# MainBoard.net
KiCad netlist of a schematic drawn in Altium Designer
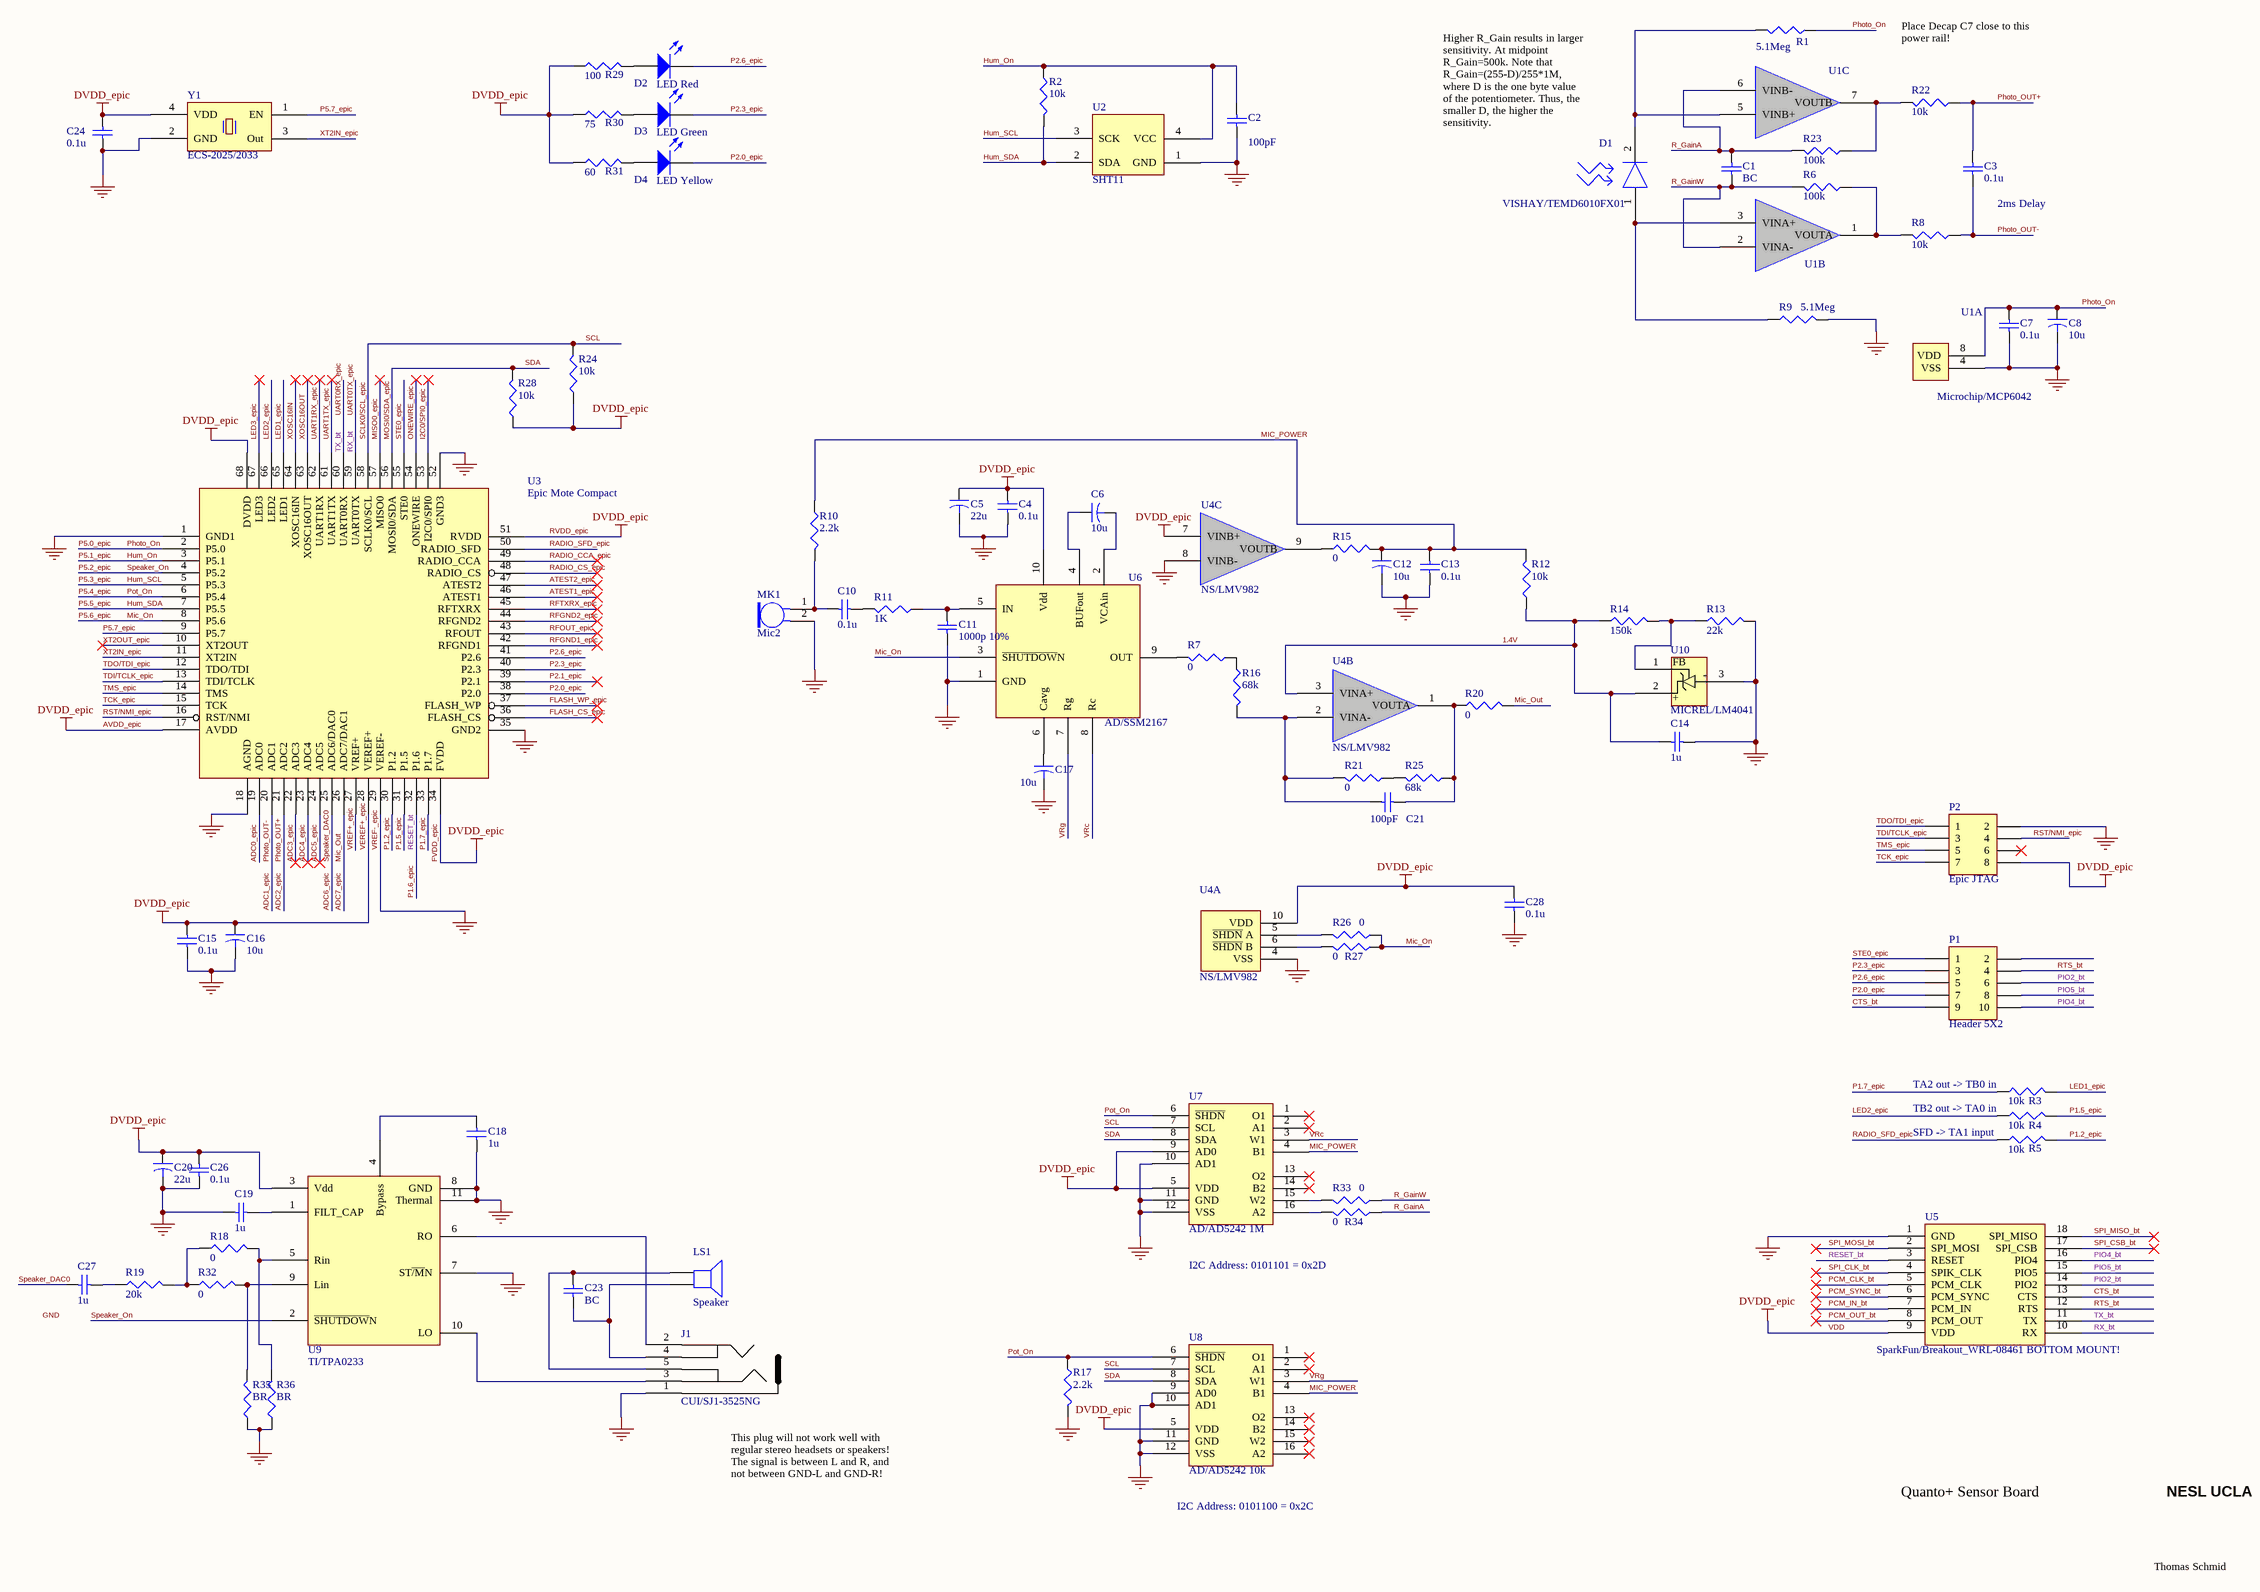
[diagram p0: MainBoard.SchDoc]

(export (version "E")
  (design (tool "Eeschema 10.0.6"))
  (components
    (comp (ref "C1")
      (value "BC")
      (footprint "CC1608-0603")
      (description "Capacitor")
      (fields (field (name "Comment") "Cap") (field (name "PUBLISHER") "Altium Limited"))
      (libsource (lib "Miscellaneous Devices") (part "Cap"))
    )
    (comp (ref "C2")
      (value "100pF")
      (footprint "CC1608-0603")
      (description "Capacitor")
      (fields (field (name "Comment") "Cap") (field (name "PUBLISHER") "Altium Limited"))
      (libsource (lib "Miscellaneous Devices") (part "Cap"))
    )
    (comp (ref "C3")
      (value "0.1u")
      (footprint "CC1608-0603")
      (description "Capacitor")
      (fields (field (name "Comment") "Cap") (field (name "PUBLISHER") "Altium Limited"))
      (libsource (lib "Miscellaneous Devices") (part "Cap"))
    )
    (comp (ref "C4")
      (value "0.1u")
      (footprint "CC1608-0603")
      (description "Capacitor")
      (fields (field (name "Comment") "Cap") (field (name "PUBLISHER") "Altium Limited"))
      (libsource (lib "Miscellaneous Devices") (part "Cap"))
    )
    (comp (ref "C5")
      (value "22u")
      (footprint "CC3216-1206")
      (description "Capacitor")
      (fields (field (name "Comment") "Cap2") (field (name "PUBLISHER") "Altium Limited"))
      (libsource (lib "Miscellaneous Devices") (part "Cap2"))
    )
    (comp (ref "C6")
      (value "10u")
      (footprint "CC1608-0603")
      (description "Capacitor")
      (fields (field (name "Comment") "Cap2") (field (name "PUBLISHER") "Altium Limited"))
      (libsource (lib "") (part "Cap2_1"))
    )
    (comp (ref "C7")
      (value "0.1u")
      (footprint "CC1608-0603")
      (description "Capacitor")
      (fields (field (name "Comment") "Cap") (field (name "PUBLISHER") "Altium Limited"))
      (libsource (lib "Miscellaneous Devices") (part "Cap"))
    )
    (comp (ref "C8")
      (value "10u")
      (footprint "CC1608-0603")
      (description "Capacitor")
      (fields (field (name "Comment") "Cap2") (field (name "PUBLISHER") "Altium Limited"))
      (libsource (lib "Miscellaneous Devices") (part "Cap2"))
    )
    (comp (ref "C10")
      (value "0.1u")
      (footprint "CC1608-0603")
      (description "Capacitor")
      (fields (field (name "Comment") "Cap") (field (name "PUBLISHER") "Altium Limited"))
      (libsource (lib "Miscellaneous Devices") (part "Cap"))
    )
    (comp (ref "C11")
      (value "1000p 10%")
      (footprint "CC1608-0603")
      (description "Capacitor")
      (fields (field (name "Comment") "Cap") (field (name "PUBLISHER") "Altium Limited"))
      (libsource (lib "Miscellaneous Devices") (part "Cap"))
    )
    (comp (ref "C12")
      (value "10u")
      (footprint "CC1608-0603")
      (description "Capacitor")
      (fields (field (name "Comment") "Cap2") (field (name "PUBLISHER") "Altium Limited"))
      (libsource (lib "Miscellaneous Devices") (part "Cap2"))
    )
    (comp (ref "C13")
      (value "0.1u")
      (footprint "CC1608-0603")
      (description "Capacitor")
      (fields (field (name "Comment") "Cap") (field (name "PUBLISHER") "Altium Limited"))
      (libsource (lib "Miscellaneous Devices") (part "Cap"))
    )
    (comp (ref "C14")
      (value "1u")
      (footprint "CC1608-0603")
      (description "Capacitor")
      (fields (field (name "Comment") "Cap") (field (name "PUBLISHER") "Altium Limited"))
      (libsource (lib "") (part "Cap_1"))
    )
    (comp (ref "C15")
      (value "0.1u")
      (footprint "CC1608-0603")
      (description "Capacitor")
      (fields (field (name "Comment") "Cap") (field (name "PUBLISHER") "Altium Limited"))
      (libsource (lib "Miscellaneous Devices") (part "Cap"))
    )
    (comp (ref "C16")
      (value "10u")
      (footprint "CC1608-0603")
      (description "Capacitor")
      (fields (field (name "Comment") "Cap2") (field (name "PUBLISHER") "Altium Limited"))
      (libsource (lib "Miscellaneous Devices") (part "Cap2"))
    )
    (comp (ref "C17")
      (value "10u")
      (footprint "CC1608-0603")
      (description "Capacitor")
      (fields (field (name "Comment") "Cap2") (field (name "PUBLISHER") "Altium Limited"))
      (libsource (lib "") (part "Cap2_1"))
    )
    (comp (ref "C18")
      (value "1u")
      (footprint "CC1608-0603")
      (description "Capacitor")
      (fields (field (name "Comment") "Cap") (field (name "PUBLISHER") "Altium Limited"))
      (libsource (lib "Miscellaneous Devices") (part "Cap"))
    )
    (comp (ref "C19")
      (value "1u")
      (footprint "CC1608-0603")
      (description "Capacitor")
      (fields (field (name "Comment") "Cap") (field (name "PUBLISHER") "Altium Limited"))
      (libsource (lib "") (part "Cap_1"))
    )
    (comp (ref "C20")
      (value "22u")
      (footprint "CC3216-1206")
      (description "Capacitor")
      (fields (field (name "Comment") "Cap2") (field (name "PUBLISHER") "Altium Limited"))
      (libsource (lib "Miscellaneous Devices") (part "Cap2"))
    )
    (comp (ref "C21")
      (value "100pF")
      (footprint "CC1608-0603")
      (description "Capacitor")
      (fields (field (name "Comment") "Cap") (field (name "PUBLISHER") "Altium Limited"))
      (libsource (lib "Miscellaneous Devices") (part "Cap"))
    )
    (comp (ref "C23")
      (value "BC")
      (footprint "CC1608-0603")
      (description "Capacitor")
      (fields (field (name "Comment") "Cap") (field (name "PUBLISHER") "Altium Limited"))
      (libsource (lib "Miscellaneous Devices") (part "Cap"))
    )
    (comp (ref "C24")
      (value "0.1u")
      (footprint "CC1608-0603")
      (description "Capacitor")
      (fields (field (name "Comment") "Cap") (field (name "PUBLISHER") "Altium Limited"))
      (libsource (lib "Miscellaneous Devices") (part "Cap"))
    )
    (comp (ref "C26")
      (value "0.1u")
      (footprint "CC1608-0603")
      (description "Capacitor")
      (fields (field (name "Comment") "Cap") (field (name "PUBLISHER") "Altium Limited"))
      (libsource (lib "Miscellaneous Devices") (part "Cap"))
    )
    (comp (ref "C27")
      (value "1u")
      (footprint "CC1608-0603")
      (description "Capacitor")
      (fields (field (name "Comment") "Cap") (field (name "PUBLISHER") "Altium Limited"))
      (libsource (lib "Miscellaneous Devices") (part "Cap"))
    )
    (comp (ref "C28")
      (value "0.1u")
      (footprint "CC1608-0603")
      (description "Capacitor")
      (fields (field (name "Comment") "Cap") (field (name "PUBLISHER") "Altium Limited"))
      (libsource (lib "Miscellaneous Devices") (part "Cap"))
    )
    (comp (ref "D1")
      (value "VISHAY/TEMD6010FX01")
      (footprint "VISHAY/TEMD6010FX01")
      (libsource (lib "Schematics") (part "VISHAY/TEMD6010FX01"))
    )
    (comp (ref "D2")
      (value "LED Red")
      (footprint "LiteOn/LTST-C150")
      (description "Typical RED, GREEN, YELLOW, AMBER GaAs LED")
      (fields (field (name "PUBLISHER") "Altium Limited"))
      (libsource (lib "Miscellaneous Devices") (part "LED2"))
    )
    (comp (ref "D3")
      (value "LED Green")
      (footprint "LiteOn/LTST-C150")
      (description "Typical RED, GREEN, YELLOW, AMBER GaAs LED")
      (fields (field (name "PUBLISHER") "Altium Limited"))
      (libsource (lib "Miscellaneous Devices") (part "LED2"))
    )
    (comp (ref "D4")
      (value "LED Yellow")
      (footprint "LiteOn/LTST-C150")
      (description "Typical RED, GREEN, YELLOW, AMBER GaAs LED")
      (fields (field (name "PUBLISHER") "Altium Limited"))
      (libsource (lib "Miscellaneous Devices") (part "LED2"))
    )
    (comp (ref "J1")
      (value "CUI/SJ1-3525NG")
      (footprint "CUI/PHONE_JACK_3.5mm")
      (libsource (lib "Schematics") (part "CUI/SJ1-3525NG"))
    )
    (comp (ref "LS1")
      (value "Speaker")
      (footprint "PIN2")
      (description "Loudspeaker")
      (fields (field (name "PUBLISHER") "Altium Limited"))
      (libsource (lib "Miscellaneous Devices") (part "Speaker"))
    )
    (comp (ref "MK1")
      (value "Mic2")
      (footprint "CUIINC/CMA-4544PF-W")
      (description "Microphone")
      (fields (field (name "PUBLISHER") "Altium Limited"))
      (libsource (lib "Miscellaneous Devices") (part "Mic2"))
    )
    (comp (ref "P1")
      (value "Header 5X2")
      (footprint "HDR2X5")
      (description "Header, 5-Pin, Dual row")
      (fields (field (name "PUBLISHER") "Altium Limited"))
      (libsource (lib "Miscellaneous Connectors") (part "Header 5X2"))
    )
    (comp (ref "P2")
      (value "Epic JTAG")
      (footprint "Thomas/Header 2x4 2mm")
      (description "Header, 4-Pin, Dual row")
      (fields (field (name "PUBLISHER") "Altium Limited"))
      (libsource (lib "Miscellaneous Connectors") (part "Header 4X2"))
    )
    (comp (ref "R1")
      (value "5.1Meg")
      (footprint "CR1608-0603")
      (description "Resistor")
      (fields (field (name "Comment") "Res3") (field (name "PUBLISHER") "Altium Limited"))
      (libsource (lib "Miscellaneous Devices") (part "Res3"))
    )
    (comp (ref "R2")
      (value "10k")
      (footprint "CR1608-0603")
      (description "Resistor")
      (fields (field (name "Comment") "Res3") (field (name "PUBLISHER") "Altium Limited"))
      (libsource (lib "Miscellaneous Devices") (part "Res3"))
    )
    (comp (ref "R3")
      (value "10k")
      (footprint "CR1608-0603")
      (description "Resistor")
      (fields (field (name "Comment") "Res3") (field (name "PUBLISHER") "Altium Limited"))
      (libsource (lib "Miscellaneous Devices") (part "Res3"))
    )
    (comp (ref "R4")
      (value "10k")
      (footprint "CR1608-0603")
      (description "Resistor")
      (fields (field (name "Comment") "Res3") (field (name "PUBLISHER") "Altium Limited"))
      (libsource (lib "Miscellaneous Devices") (part "Res3"))
    )
    (comp (ref "R5")
      (value "10k")
      (footprint "CR1608-0603")
      (description "Resistor")
      (fields (field (name "Comment") "Res3") (field (name "PUBLISHER") "Altium Limited"))
      (libsource (lib "Miscellaneous Devices") (part "Res3"))
    )
    (comp (ref "R6")
      (value "100k")
      (footprint "CR1608-0603")
      (description "Resistor")
      (fields (field (name "Comment") "Res3") (field (name "PUBLISHER") "Altium Limited"))
      (libsource (lib "Miscellaneous Devices") (part "Res3"))
    )
    (comp (ref "R7")
      (value "0")
      (footprint "CR1608-0603")
      (description "Resistor")
      (fields (field (name "Comment") "Res3") (field (name "PUBLISHER") "Altium Limited"))
      (libsource (lib "Miscellaneous Devices") (part "Res3"))
    )
    (comp (ref "R8")
      (value "10k")
      (footprint "CR1608-0603")
      (description "Resistor")
      (fields (field (name "Comment") "Res3") (field (name "PUBLISHER") "Altium Limited"))
      (libsource (lib "Miscellaneous Devices") (part "Res3"))
    )
    (comp (ref "R9")
      (value "5.1Meg")
      (footprint "CR1608-0603")
      (description "Resistor")
      (fields (field (name "Comment") "Res3") (field (name "PUBLISHER") "Altium Limited"))
      (libsource (lib "Miscellaneous Devices") (part "Res3"))
    )
    (comp (ref "R10")
      (value "2.2k")
      (footprint "CR1608-0603")
      (description "Resistor")
      (fields (field (name "Comment") "Res3") (field (name "PUBLISHER") "Altium Limited"))
      (libsource (lib "Miscellaneous Devices") (part "Res3"))
    )
    (comp (ref "R11")
      (value "1K")
      (footprint "CR1608-0603")
      (description "Resistor")
      (fields (field (name "Comment") "Res3") (field (name "PUBLISHER") "Altium Limited"))
      (libsource (lib "Miscellaneous Devices") (part "Res3"))
    )
    (comp (ref "R12")
      (value "10k")
      (footprint "CR1608-0603")
      (description "Resistor")
      (fields (field (name "Comment") "Res3") (field (name "PUBLISHER") "Altium Limited"))
      (libsource (lib "Miscellaneous Devices") (part "Res3"))
    )
    (comp (ref "R13")
      (value "22k")
      (footprint "CR1608-0603")
      (description "Resistor")
      (fields (field (name "Comment") "Res3") (field (name "PUBLISHER") "Altium Limited"))
      (libsource (lib "Miscellaneous Devices") (part "Res3"))
    )
    (comp (ref "R14")
      (value "150k")
      (footprint "CR1608-0603")
      (description "Resistor")
      (fields (field (name "Comment") "Res3") (field (name "PUBLISHER") "Altium Limited"))
      (libsource (lib "Miscellaneous Devices") (part "Res3"))
    )
    (comp (ref "R15")
      (value "0")
      (footprint "CR1608-0603")
      (description "Resistor")
      (fields (field (name "Comment") "Res3") (field (name "PUBLISHER") "Altium Limited"))
      (libsource (lib "Miscellaneous Devices") (part "Res3"))
    )
    (comp (ref "R16")
      (value "68k")
      (footprint "CR1608-0603")
      (description "Resistor")
      (fields (field (name "Comment") "Res3") (field (name "PUBLISHER") "Altium Limited"))
      (libsource (lib "") (part "Res3_1"))
    )
    (comp (ref "R17")
      (value "2.2k")
      (footprint "CR1608-0603")
      (description "Resistor")
      (fields (field (name "Comment") "Res3") (field (name "PUBLISHER") "Altium Limited"))
      (libsource (lib "Miscellaneous Devices") (part "Res3"))
    )
    (comp (ref "R18")
      (value "0")
      (footprint "CR1608-0603")
      (description "Resistor")
      (fields (field (name "Comment") "Res3") (field (name "PUBLISHER") "Altium Limited"))
      (libsource (lib "Miscellaneous Devices") (part "Res3"))
    )
    (comp (ref "R19")
      (value "20k")
      (footprint "CR1608-0603")
      (description "Resistor")
      (fields (field (name "Comment") "Res3") (field (name "PUBLISHER") "Altium Limited"))
      (libsource (lib "Miscellaneous Devices") (part "Res3"))
    )
    (comp (ref "R20")
      (value "0")
      (footprint "CR1608-0603")
      (description "Resistor")
      (fields (field (name "Comment") "Res3") (field (name "PUBLISHER") "Altium Limited"))
      (libsource (lib "Miscellaneous Devices") (part "Res3"))
    )
    (comp (ref "R21")
      (value "0")
      (footprint "CR1608-0603")
      (description "Resistor")
      (fields (field (name "Comment") "Res3") (field (name "PUBLISHER") "Altium Limited"))
      (libsource (lib "Miscellaneous Devices") (part "Res3"))
    )
    (comp (ref "R22")
      (value "10k")
      (footprint "CR1608-0603")
      (description "Resistor")
      (fields (field (name "Comment") "Res3") (field (name "PUBLISHER") "Altium Limited"))
      (libsource (lib "Miscellaneous Devices") (part "Res3"))
    )
    (comp (ref "R23")
      (value "100k")
      (footprint "CR1608-0603")
      (description "Resistor")
      (fields (field (name "Comment") "Res3") (field (name "PUBLISHER") "Altium Limited"))
      (libsource (lib "Miscellaneous Devices") (part "Res3"))
    )
    (comp (ref "R24")
      (value "10k")
      (footprint "CR1608-0603")
      (description "Resistor")
      (fields (field (name "Comment") "Res3") (field (name "PUBLISHER") "Altium Limited"))
      (libsource (lib "Miscellaneous Devices") (part "Res3"))
    )
    (comp (ref "R25")
      (value "68k")
      (footprint "CR1608-0603")
      (description "Resistor")
      (fields (field (name "Comment") "Res3") (field (name "PUBLISHER") "Altium Limited"))
      (libsource (lib "Miscellaneous Devices") (part "Res3"))
    )
    (comp (ref "R26")
      (value "0")
      (footprint "CR1608-0603")
      (description "Resistor")
      (fields (field (name "Comment") "Res3") (field (name "PUBLISHER") "Altium Limited"))
      (libsource (lib "Miscellaneous Devices") (part "Res3"))
    )
    (comp (ref "R27")
      (value "0")
      (footprint "CR1608-0603")
      (description "Resistor")
      (fields (field (name "Comment") "Res3") (field (name "PUBLISHER") "Altium Limited"))
      (libsource (lib "Miscellaneous Devices") (part "Res3"))
    )
    (comp (ref "R28")
      (value "10k")
      (footprint "CR1608-0603")
      (description "Resistor")
      (fields (field (name "Comment") "Res3") (field (name "PUBLISHER") "Altium Limited"))
      (libsource (lib "Miscellaneous Devices") (part "Res3"))
    )
    (comp (ref "R29")
      (value "100")
      (footprint "CR1608-0603")
      (description "Resistor")
      (fields (field (name "Comment") "Res3") (field (name "PUBLISHER") "Altium Limited"))
      (libsource (lib "Miscellaneous Devices") (part "Res3"))
    )
    (comp (ref "R30")
      (value "75")
      (footprint "CR1608-0603")
      (description "Resistor")
      (fields (field (name "Comment") "Res3") (field (name "PUBLISHER") "Altium Limited"))
      (libsource (lib "Miscellaneous Devices") (part "Res3"))
    )
    (comp (ref "R31")
      (value "60")
      (footprint "CR1608-0603")
      (description "Resistor")
      (fields (field (name "Comment") "Res3") (field (name "PUBLISHER") "Altium Limited"))
      (libsource (lib "Miscellaneous Devices") (part "Res3"))
    )
    (comp (ref "R32")
      (value "0")
      (footprint "CR1608-0603")
      (description "Resistor")
      (fields (field (name "Comment") "Res3") (field (name "PUBLISHER") "Altium Limited"))
      (libsource (lib "Miscellaneous Devices") (part "Res3"))
    )
    (comp (ref "R33")
      (value "0")
      (footprint "CR1608-0603")
      (description "Resistor")
      (fields (field (name "Comment") "Res3") (field (name "PUBLISHER") "Altium Limited"))
      (libsource (lib "Miscellaneous Devices") (part "Res3"))
    )
    (comp (ref "R34")
      (value "0")
      (footprint "CR1608-0603")
      (description "Resistor")
      (fields (field (name "Comment") "Res3") (field (name "PUBLISHER") "Altium Limited"))
      (libsource (lib "Miscellaneous Devices") (part "Res3"))
    )
    (comp (ref "R35")
      (value "BR")
      (footprint "CR1608-0603")
      (description "Resistor")
      (fields (field (name "Comment") "Res3") (field (name "PUBLISHER") "Altium Limited"))
      (libsource (lib "Miscellaneous Devices") (part "Res3"))
    )
    (comp (ref "R36")
      (value "BR")
      (footprint "CR1608-0603")
      (description "Resistor")
      (fields (field (name "Comment") "Res3") (field (name "PUBLISHER") "Altium Limited"))
      (libsource (lib "Miscellaneous Devices") (part "Res3"))
    )
    (comp (ref "U1")
      (value "Microchip/MCP6042")
      (footprint "SOIC127P600X175-8N")
      (libsource (lib "Schematics") (part "Microchip/MCP6042"))
    )
    (comp (ref "U2")
      (value "SHT11")
      (footprint "Sensirion/SHT11")
      (libsource (lib "Schematics") (part "SHT11"))
    )
    (comp (ref "U3")
      (value "Epic Mote Compact")
      (footprint "UCB/Epic_Quanto_Header")
      (libsource (lib "Schematics") (part "Epic Mote Compact"))
    )
    (comp (ref "U4")
      (value "NS/LMV982")
      (footprint "MSOP10")
      (libsource (lib "Schematics") (part "NS/LMV982"))
    )
    (comp (ref "U5")
      (value "SparkFun/Breakout_WRL-08461 BOTTOM MOUNT!")
      (footprint "SparkFun/Breakout_WRL-084")
      (libsource (lib "Schematics") (part "SparkFun/Breakout_WRL-084"))
    )
    (comp (ref "U6")
      (value "AD/SSM2167")
      (footprint "MSOP127P600-8N")
      (libsource (lib "Schematics") (part "AD/SSM2167"))
    )
    (comp (ref "U7")
      (value "AD/AD5242 1M")
      (footprint "SOIC127P600X175-16N")
      (libsource (lib "Schematics") (part "AD/AD5242"))
    )
    (comp (ref "U8")
      (value "AD/AD5242 10k")
      (footprint "SOIC127P600X175-16N")
      (libsource (lib "Schematics") (part "AD/AD5242"))
    )
    (comp (ref "U9")
      (value "TI/TPA0233")
      (footprint "TSSOP50P480X107_HS-10N")
      (libsource (lib "Schematics") (part "TI/TPA0233"))
    )
    (comp (ref "U10")
      (value "MICREL/LM4041")
      (footprint "SOT231 (M3)")
      (libsource (lib "Schematics") (part "MICREL/LM4041"))
    )
    (comp (ref "Y1")
      (value "ECS-2025/2033")
      (footprint "ECS_2025/2033")
      (libsource (lib "Schematics") (part "ECS-2025/2033"))
    )
  )
  (nets
    (net (code "1") (name "/1.4V") (class "Default")
      (node (ref "C14") (pin "1") (pinfunction "1_1") (pintype "passive"))
      (node (ref "R12") (pin "1") (pinfunction "1_1") (pintype "passive"))
      (node (ref "R14") (pin "1") (pinfunction "1_1") (pintype "passive"))
      (node (ref "U10") (pin "2") (pinfunction "2_2") (pintype "passive"))
      (node (ref "U4") (pin "3") (pinfunction "VINA+_3") (pintype "passive"))
    )
    (net (code "2") (name "/ADC0_epic") (class "Default")
      (node (ref "U3") (pin "19") (pinfunction "ADC0_19") (pintype "passive"))
    )
    (net (code "3") (name "/ADC1_epic") (class "Default")
      (node (ref "C3") (pin "2") (pinfunction "2_2") (pintype "passive"))
      (node (ref "R8") (pin "1") (pinfunction "1_1") (pintype "passive"))
      (node (ref "U3") (pin "20") (pinfunction "ADC1_20") (pintype "passive"))
    )
    (net (code "4") (name "/ADC2_epic") (class "Default")
      (node (ref "C3") (pin "1") (pinfunction "1_1") (pintype "passive"))
      (node (ref "R22") (pin "1") (pinfunction "1_1") (pintype "passive"))
      (node (ref "U3") (pin "21") (pinfunction "ADC2_21") (pintype "passive"))
    )
    (net (code "5") (name "/ADC3_epic") (class "Default")
      (node (ref "U3") (pin "22") (pinfunction "ADC3_22") (pintype "passive+no_connect"))
    )
    (net (code "6") (name "/ADC4_epic") (class "Default")
      (node (ref "U3") (pin "23") (pinfunction "ADC4_23") (pintype "passive+no_connect"))
    )
    (net (code "7") (name "/ADC5_epic") (class "Default")
      (node (ref "U3") (pin "24") (pinfunction "ADC5_24") (pintype "passive+no_connect"))
    )
    (net (code "8") (name "/ADC6_epic") (class "Default")
      (node (ref "C27") (pin "2") (pinfunction "2_2") (pintype "passive"))
      (node (ref "U3") (pin "25") (pinfunction "ADC6/DAC0_25") (pintype "passive"))
    )
    (net (code "9") (name "/ADC7_epic") (class "Default")
      (node (ref "R20") (pin "2") (pinfunction "2_2") (pintype "passive"))
      (node (ref "U3") (pin "26") (pinfunction "ADC7/DAC1_26") (pintype "passive"))
    )
    (net (code "10") (name "/ATEST1_epic") (class "Default")
      (node (ref "U3") (pin "46") (pinfunction "ATEST1_46") (pintype "passive+no_connect"))
    )
    (net (code "11") (name "/ATEST2_epic") (class "Default")
      (node (ref "U3") (pin "47") (pinfunction "ATEST2_47") (pintype "passive+no_connect"))
    )
    (net (code "12") (name "/CTS_bt") (class "Default")
      (node (ref "P1") (pin "9") (pinfunction "9_9") (pintype "passive"))
      (node (ref "U5") (pin "13") (pinfunction "CTS_13") (pintype "passive"))
    )
    (net (code "13") (name "/FLASH_CS_epic") (class "Default")
      (node (ref "U3") (pin "36") (pinfunction "FLASH_CS_36") (pintype "passive+no_connect"))
    )
    (net (code "14") (name "/FLASH_WP_epic") (class "Default")
      (node (ref "U3") (pin "37") (pinfunction "FLASH_WP_37") (pintype "passive+no_connect"))
    )
    (net (code "15") (name "/Hum_On") (class "Default")
      (node (ref "C2") (pin "2") (pinfunction "2_2") (pintype "passive"))
      (node (ref "R2") (pin "1") (pinfunction "1_1") (pintype "passive"))
      (node (ref "U2") (pin "4") (pinfunction "VCC_4") (pintype "power_in"))
      (node (ref "U3") (pin "3") (pinfunction "P5.1_3") (pintype "passive"))
    )
    (net (code "16") (name "/Hum_SCL") (class "Default")
      (node (ref "U2") (pin "3") (pinfunction "SCK_3") (pintype "passive"))
      (node (ref "U3") (pin "5") (pinfunction "P5.3_5") (pintype "passive"))
    )
    (net (code "17") (name "/Hum_SDA") (class "Default")
      (node (ref "R2") (pin "2") (pinfunction "2_2") (pintype "passive"))
      (node (ref "U2") (pin "2") (pinfunction "SDA_2") (pintype "passive"))
      (node (ref "U3") (pin "7") (pinfunction "P5.5_7") (pintype "passive"))
    )
    (net (code "18") (name "/I2C0{slash}SPI0_epic") (class "Default")
      (node (ref "U3") (pin "53") (pinfunction "I2C0/SPI0_53") (pintype "passive+no_connect"))
    )
    (net (code "19") (name "/LED1_epic") (class "Default")
      (node (ref "R3") (pin "2") (pinfunction "2_2") (pintype "passive"))
      (node (ref "U3") (pin "65") (pinfunction "LED1_65") (pintype "passive"))
    )
    (net (code "20") (name "/LED2_epic") (class "Default")
      (node (ref "R4") (pin "1") (pinfunction "1_1") (pintype "passive"))
      (node (ref "U3") (pin "66") (pinfunction "LED2_66") (pintype "passive"))
    )
    (net (code "21") (name "/LED3_epic") (class "Default")
      (node (ref "U3") (pin "67") (pinfunction "LED3_67") (pintype "passive+no_connect"))
    )
    (net (code "22") (name "/MIC_POWER") (class "Default")
      (node (ref "C12") (pin "1") (pinfunction "1_1") (pintype "passive"))
      (node (ref "C13") (pin "1") (pinfunction "1_1") (pintype "passive"))
      (node (ref "R10") (pin "1") (pinfunction "1_1") (pintype "passive"))
      (node (ref "R12") (pin "2") (pinfunction "2_2") (pintype "passive"))
      (node (ref "R15") (pin "2") (pinfunction "2_2") (pintype "passive"))
      (node (ref "U7") (pin "4") (pinfunction "B1_4") (pintype "passive"))
      (node (ref "U8") (pin "4") (pinfunction "B1_4") (pintype "passive"))
    )
    (net (code "23") (name "/MISO0_epic") (class "Default")
      (node (ref "U3") (pin "57") (pinfunction "MISO0_57") (pintype "passive+no_connect"))
    )
    (net (code "24") (name "/MOSI0{slash}SDA_epic") (class "Default")
      (node (ref "R28") (pin "2") (pinfunction "2_2") (pintype "passive"))
      (node (ref "U3") (pin "56") (pinfunction "MOSI0/SDA_56") (pintype "passive"))
      (node (ref "U7") (pin "8") (pinfunction "SDA_8") (pintype "passive"))
      (node (ref "U8") (pin "8") (pinfunction "SDA_8") (pintype "passive"))
    )
    (net (code "25") (name "/Mic_On") (class "Default")
      (node (ref "R26") (pin "2") (pinfunction "2_2") (pintype "passive"))
      (node (ref "R27") (pin "2") (pinfunction "2_2") (pintype "passive"))
      (node (ref "U3") (pin "8") (pinfunction "P5.6_8") (pintype "passive"))
      (node (ref "U6") (pin "3") (pinfunction "~{SHUTDOW}N_3") (pintype "passive"))
    )
    (net (code "26") (name "/ONEWIRE_epic") (class "Default")
      (node (ref "U3") (pin "54") (pinfunction "ONEWIRE_54") (pintype "passive+no_connect"))
    )
    (net (code "27") (name "/P1.2_epic") (class "Default")
      (node (ref "R5") (pin "2") (pinfunction "2_2") (pintype "passive"))
      (node (ref "U3") (pin "30") (pinfunction "P1.2_30") (pintype "passive"))
    )
    (net (code "28") (name "/P1.5_epic") (class "Default")
      (node (ref "R4") (pin "2") (pinfunction "2_2") (pintype "passive"))
      (node (ref "U3") (pin "31") (pinfunction "P1.5_31") (pintype "passive"))
    )
    (net (code "29") (name "/P1.6_epic") (class "Default")
      (node (ref "U3") (pin "32") (pinfunction "P1.6_32") (pintype "passive"))
      (node (ref "U5") (pin "3") (pinfunction "RESET_3") (pintype "passive"))
    )
    (net (code "30") (name "/P1.7_epic") (class "Default")
      (node (ref "R3") (pin "1") (pinfunction "1_1") (pintype "passive"))
      (node (ref "U3") (pin "33") (pinfunction "P1.7_33") (pintype "passive"))
    )
    (net (code "31") (name "/P2.0_epic") (class "Default")
      (node (ref "D4") (pin "2") (pinfunction "K_2") (pintype "passive"))
      (node (ref "P1") (pin "7") (pinfunction "7_7") (pintype "passive"))
      (node (ref "U3") (pin "38") (pinfunction "P2.0_38") (pintype "passive"))
    )
    (net (code "32") (name "/P2.1_epic") (class "Default")
      (node (ref "U3") (pin "39") (pinfunction "P2.1_39") (pintype "passive+no_connect"))
    )
    (net (code "33") (name "/P2.3_epic") (class "Default")
      (node (ref "D3") (pin "2") (pinfunction "K_2") (pintype "passive"))
      (node (ref "P1") (pin "3") (pinfunction "3_3") (pintype "passive"))
      (node (ref "U3") (pin "40") (pinfunction "P2.3_40") (pintype "passive"))
    )
    (net (code "34") (name "/P2.6_epic") (class "Default")
      (node (ref "D2") (pin "2") (pinfunction "K_2") (pintype "passive"))
      (node (ref "P1") (pin "5") (pinfunction "5_5") (pintype "passive"))
      (node (ref "U3") (pin "41") (pinfunction "P2.6_41") (pintype "passive"))
    )
    (net (code "35") (name "/P5.0_epic") (class "Default")
      (node (ref "C7") (pin "1") (pinfunction "1_1") (pintype "passive"))
      (node (ref "C8") (pin "1") (pinfunction "1_1") (pintype "passive"))
      (node (ref "R1") (pin "2") (pinfunction "2_2") (pintype "passive"))
      (node (ref "U1") (pin "8") (pinfunction "VDD_8") (pintype "power_in"))
      (node (ref "U3") (pin "2") (pinfunction "P5.0_2") (pintype "passive"))
    )
    (net (code "36") (name "/P5.2_epic") (class "Default")
      (node (ref "U3") (pin "4") (pinfunction "P5.2_4") (pintype "passive"))
      (node (ref "U9") (pin "2") (pinfunction "~{SHUTDOW}N_2") (pintype "passive"))
    )
    (net (code "37") (name "/P5.4_epic") (class "Default")
      (node (ref "R17") (pin "1") (pinfunction "1_1") (pintype "passive"))
      (node (ref "U3") (pin "6") (pinfunction "P5.4_6") (pintype "passive"))
      (node (ref "U7") (pin "6") (pinfunction "~{SHDN}_6") (pintype "passive"))
      (node (ref "U8") (pin "6") (pinfunction "~{SHDN}_6") (pintype "passive"))
    )
    (net (code "38") (name "/P5.7_epic") (class "Default")
      (node (ref "U3") (pin "9") (pinfunction "P5.7_9") (pintype "passive"))
      (node (ref "Y1") (pin "1") (pinfunction "EN_1") (pintype "passive"))
    )
    (net (code "39") (name "/PCM_CLK_bt") (class "Default")
      (node (ref "U5") (pin "5") (pinfunction "PCM_CLK_5") (pintype "passive+no_connect"))
    )
    (net (code "40") (name "/PCM_IN_bt") (class "Default")
      (node (ref "U5") (pin "7") (pinfunction "PCM_IN_7") (pintype "passive+no_connect"))
    )
    (net (code "41") (name "/PCM_OUT_bt") (class "Default")
      (node (ref "U5") (pin "8") (pinfunction "PCM_OUT_8") (pintype "passive+no_connect"))
    )
    (net (code "42") (name "/PCM_SYNC_bt") (class "Default")
      (node (ref "U5") (pin "6") (pinfunction "PCM_SYNC_6") (pintype "passive+no_connect"))
    )
    (net (code "43") (name "/PIO2_bt") (class "Default")
      (node (ref "P1") (pin "6") (pinfunction "6_6") (pintype "passive"))
      (node (ref "U5") (pin "14") (pinfunction "PIO2_14") (pintype "passive"))
    )
    (net (code "44") (name "/PIO4_bt") (class "Default")
      (node (ref "P1") (pin "10") (pinfunction "10_10") (pintype "passive"))
      (node (ref "U5") (pin "16") (pinfunction "PIO4_16") (pintype "passive"))
    )
    (net (code "45") (name "/PIO5_bt") (class "Default")
      (node (ref "P1") (pin "8") (pinfunction "8_8") (pintype "passive"))
      (node (ref "U5") (pin "15") (pinfunction "PIO5_15") (pintype "passive"))
    )
    (net (code "46") (name "/RADIO_CCA_epic") (class "Default")
      (node (ref "U3") (pin "49") (pinfunction "RADIO_CCA_49") (pintype "passive+no_connect"))
    )
    (net (code "47") (name "/RADIO_CS_epic") (class "Default")
      (node (ref "U3") (pin "48") (pinfunction "RADIO_CS_48") (pintype "passive+no_connect"))
    )
    (net (code "48") (name "/RADIO_SFD_epic") (class "Default")
      (node (ref "R5") (pin "1") (pinfunction "1_1") (pintype "passive"))
      (node (ref "U3") (pin "50") (pinfunction "RADIO_SFD_50") (pintype "passive"))
    )
    (net (code "49") (name "/RFGND1_epic") (class "Default")
      (node (ref "U3") (pin "42") (pinfunction "RFGND1_42") (pintype "passive+no_connect"))
    )
    (net (code "50") (name "/RFGND2_epic") (class "Default")
      (node (ref "U3") (pin "44") (pinfunction "RFGND2_44") (pintype "passive+no_connect"))
    )
    (net (code "51") (name "/RFOUT_epic") (class "Default")
      (node (ref "U3") (pin "43") (pinfunction "RFOUT_43") (pintype "passive+no_connect"))
    )
    (net (code "52") (name "/RFTXRX_epic") (class "Default")
      (node (ref "U3") (pin "45") (pinfunction "RFTXRX_45") (pintype "passive+no_connect"))
    )
    (net (code "53") (name "/RST{slash}NMI_epic") (class "Default")
      (node (ref "P2") (pin "4") (pinfunction "4_4") (pintype "passive"))
      (node (ref "U3") (pin "16") (pinfunction "RST/NMI_16") (pintype "passive"))
    )
    (net (code "54") (name "/RTS_bt") (class "Default")
      (node (ref "P1") (pin "4") (pinfunction "4_4") (pintype "passive"))
      (node (ref "U5") (pin "12") (pinfunction "RTS_12") (pintype "passive"))
    )
    (net (code "55") (name "/RX_bt") (class "Default")
      (node (ref "U3") (pin "59") (pinfunction "UART0TX_59") (pintype "passive"))
      (node (ref "U5") (pin "10") (pinfunction "RX_10") (pintype "passive"))
    )
    (net (code "56") (name "/R_GainA") (class "Default")
      (node (ref "C1") (pin "1") (pinfunction "1_1") (pintype "passive"))
      (node (ref "R23") (pin "2") (pinfunction "2_2") (pintype "passive"))
      (node (ref "R34") (pin "2") (pinfunction "2_2") (pintype "passive"))
      (node (ref "U1") (pin "6") (pinfunction "VINB-_6") (pintype "passive"))
    )
    (net (code "57") (name "/R_GainW") (class "Default")
      (node (ref "C1") (pin "2") (pinfunction "2_2") (pintype "passive"))
      (node (ref "R33") (pin "2") (pinfunction "2_2") (pintype "passive"))
      (node (ref "R6") (pin "2") (pinfunction "2_2") (pintype "passive"))
      (node (ref "U1") (pin "2") (pinfunction "VINA-_2") (pintype "passive"))
    )
    (net (code "58") (name "/SCL") (class "Default")
      (node (ref "R24") (pin "2") (pinfunction "2_2") (pintype "passive"))
      (node (ref "U3") (pin "58") (pinfunction "SCLK0/SCL_58") (pintype "passive"))
      (node (ref "U7") (pin "7") (pinfunction "SCL_7") (pintype "passive"))
      (node (ref "U8") (pin "7") (pinfunction "SCL_7") (pintype "passive"))
    )
    (net (code "59") (name "/SPI_CLK_bt") (class "Default")
      (node (ref "U5") (pin "4") (pinfunction "SPIK_CLK_4") (pintype "passive+no_connect"))
    )
    (net (code "60") (name "/SPI_CSB_bt") (class "Default")
      (node (ref "U5") (pin "17") (pinfunction "SPI_CSB_17") (pintype "passive+no_connect"))
    )
    (net (code "61") (name "/SPI_MISO_bt") (class "Default")
      (node (ref "U5") (pin "18") (pinfunction "SPI_MISO_18") (pintype "passive+no_connect"))
    )
    (net (code "62") (name "/SPI_MOSI_bt") (class "Default")
      (node (ref "U5") (pin "2") (pinfunction "SPI_MOSI_2") (pintype "passive+no_connect"))
    )
    (net (code "63") (name "/STE0_epic") (class "Default")
      (node (ref "P1") (pin "1") (pinfunction "1_1") (pintype "passive"))
      (node (ref "U3") (pin "55") (pinfunction "STE0_55") (pintype "passive"))
    )
    (net (code "64") (name "/TCK_epic") (class "Default")
      (node (ref "P2") (pin "7") (pinfunction "7_7") (pintype "passive"))
      (node (ref "U3") (pin "15") (pinfunction "TCK_15") (pintype "passive"))
    )
    (net (code "65") (name "/TDI{slash}TCLK_epic") (class "Default")
      (node (ref "P2") (pin "3") (pinfunction "3_3") (pintype "passive"))
      (node (ref "U3") (pin "13") (pinfunction "TDI/TCLK_13") (pintype "passive"))
    )
    (net (code "66") (name "/TDO{slash}TDI_epic") (class "Default")
      (node (ref "P2") (pin "1") (pinfunction "1_1") (pintype "passive"))
      (node (ref "U3") (pin "12") (pinfunction "TDO/TDI_12") (pintype "passive"))
    )
    (net (code "67") (name "/TMS_epic") (class "Default")
      (node (ref "P2") (pin "5") (pinfunction "5_5") (pintype "passive"))
      (node (ref "U3") (pin "14") (pinfunction "TMS_14") (pintype "passive"))
    )
    (net (code "68") (name "/TX_bt") (class "Default")
      (node (ref "U3") (pin "60") (pinfunction "UART0RX_60") (pintype "passive"))
      (node (ref "U5") (pin "11") (pinfunction "TX_11") (pintype "passive"))
    )
    (net (code "69") (name "/UART1RX_epic") (class "Default")
      (node (ref "U3") (pin "62") (pinfunction "UART1RX_62") (pintype "passive+no_connect"))
    )
    (net (code "70") (name "/UART1TX_epic") (class "Default")
      (node (ref "U3") (pin "61") (pinfunction "UART1TX_61") (pintype "passive+no_connect"))
    )
    (net (code "71") (name "/VREF+_epic") (class "Default")
      (node (ref "U3") (pin "27") (pinfunction "VREF+_27") (pintype "passive"))
    )
    (net (code "72") (name "/VRc") (class "Default")
      (node (ref "U6") (pin "8") (pinfunction "Rc_8") (pintype "passive"))
      (node (ref "U7") (pin "3") (pinfunction "W1_3") (pintype "passive"))
    )
    (net (code "73") (name "/VRg") (class "Default")
      (node (ref "U6") (pin "7") (pinfunction "Rg_7") (pintype "passive"))
      (node (ref "U8") (pin "3") (pinfunction "W1_3") (pintype "passive"))
    )
    (net (code "74") (name "/XOSC16IN") (class "Default")
      (node (ref "U3") (pin "64") (pinfunction "XOSC16IN_64") (pintype "passive+no_connect"))
    )
    (net (code "75") (name "/XOSC16OUT") (class "Default")
      (node (ref "U3") (pin "63") (pinfunction "XOSC16OUT_63") (pintype "passive+no_connect"))
    )
    (net (code "76") (name "/XT2IN_epic") (class "Default")
      (node (ref "U3") (pin "11") (pinfunction "XT2IN_11") (pintype "passive"))
      (node (ref "Y1") (pin "3") (pinfunction "Out_3") (pintype "passive"))
    )
    (net (code "77") (name "/XT2OUT_epic") (class "Default")
      (node (ref "U3") (pin "10") (pinfunction "XT2OUT_10") (pintype "passive+no_connect"))
    )
    (net (code "78") (name "DVDD_epic") (class "Default")
      (node (ref "C15") (pin "1") (pinfunction "1_1") (pintype "passive"))
      (node (ref "C16") (pin "1") (pinfunction "1_1") (pintype "passive"))
      (node (ref "C20") (pin "1") (pinfunction "1_1") (pintype "passive"))
      (node (ref "C24") (pin "1") (pinfunction "1_1") (pintype "passive"))
      (node (ref "C26") (pin "1") (pinfunction "1_1") (pintype "passive"))
      (node (ref "C28") (pin "1") (pinfunction "1_1") (pintype "passive"))
      (node (ref "C4") (pin "1") (pinfunction "1_1") (pintype "passive"))
      (node (ref "C5") (pin "1") (pinfunction "1_1") (pintype "passive"))
      (node (ref "P2") (pin "8") (pinfunction "8_8") (pintype "passive"))
      (node (ref "R24") (pin "1") (pinfunction "1_1") (pintype "passive"))
      (node (ref "R28") (pin "1") (pinfunction "1_1") (pintype "passive"))
      (node (ref "R29") (pin "1") (pinfunction "1_1") (pintype "passive"))
      (node (ref "R30") (pin "1") (pinfunction "1_1") (pintype "passive"))
      (node (ref "R31") (pin "1") (pinfunction "1_1") (pintype "passive"))
      (node (ref "U3") (pin "17") (pinfunction "AVDD_17") (pintype "passive"))
      (node (ref "U3") (pin "28") (pinfunction "VEREF+_28") (pintype "passive"))
      (node (ref "U3") (pin "34") (pinfunction "FVDD_34") (pintype "passive"))
      (node (ref "U3") (pin "51") (pinfunction "RVDD_51") (pintype "passive"))
      (node (ref "U3") (pin "68") (pinfunction "DVDD_68") (pintype "passive"))
      (node (ref "U4") (pin "10") (pinfunction "VDD_10") (pintype "power_in"))
      (node (ref "U4") (pin "7") (pinfunction "VINB+_7") (pintype "passive"))
      (node (ref "U5") (pin "9") (pinfunction "VDD_9") (pintype "passive"))
      (node (ref "U6") (pin "10") (pinfunction "Vdd_10") (pintype "passive"))
      (node (ref "U7") (pin "5") (pinfunction "VDD_5") (pintype "passive"))
      (node (ref "U7") (pin "9") (pinfunction "AD0_9") (pintype "passive"))
      (node (ref "U8") (pin "5") (pinfunction "VDD_5") (pintype "passive"))
      (node (ref "U9") (pin "3") (pinfunction "Vdd_3") (pintype "passive"))
      (node (ref "Y1") (pin "4") (pinfunction "VDD_4") (pintype "passive"))
    )
    (net (code "79") (name "GND") (class "Default")
      (node (ref "C11") (pin "2") (pinfunction "2_2") (pintype "passive"))
      (node (ref "C12") (pin "2") (pinfunction "2_2") (pintype "passive"))
      (node (ref "C13") (pin "2") (pinfunction "2_2") (pintype "passive"))
      (node (ref "C14") (pin "2") (pinfunction "2_2") (pintype "passive"))
      (node (ref "C15") (pin "2") (pinfunction "2_2") (pintype "passive"))
      (node (ref "C16") (pin "2") (pinfunction "2_2") (pintype "passive"))
      (node (ref "C17") (pin "2") (pinfunction "2_2") (pintype "passive"))
      (node (ref "C18") (pin "2") (pinfunction "2_2") (pintype "passive"))
      (node (ref "C19") (pin "1") (pinfunction "1_1") (pintype "passive"))
      (node (ref "C2") (pin "1") (pinfunction "1_1") (pintype "passive"))
      (node (ref "C20") (pin "2") (pinfunction "2_2") (pintype "passive"))
      (node (ref "C24") (pin "2") (pinfunction "2_2") (pintype "passive"))
      (node (ref "C26") (pin "2") (pinfunction "2_2") (pintype "passive"))
      (node (ref "C28") (pin "2") (pinfunction "2_2") (pintype "passive"))
      (node (ref "C4") (pin "2") (pinfunction "2_2") (pintype "passive"))
      (node (ref "C5") (pin "2") (pinfunction "2_2") (pintype "passive"))
      (node (ref "C7") (pin "2") (pinfunction "2_2") (pintype "passive"))
      (node (ref "C8") (pin "2") (pinfunction "2_2") (pintype "passive"))
      (node (ref "J1") (pin "1") (pinfunction "1_1") (pintype "passive"))
      (node (ref "MK1") (pin "2") (pinfunction "2_2") (pintype "passive"))
      (node (ref "P2") (pin "2") (pinfunction "2_2") (pintype "passive"))
      (node (ref "R13") (pin "2") (pinfunction "2_2") (pintype "passive"))
      (node (ref "R17") (pin "2") (pinfunction "2_2") (pintype "passive"))
      (node (ref "R35") (pin "1") (pinfunction "1_1") (pintype "passive"))
      (node (ref "R36") (pin "1") (pinfunction "1_1") (pintype "passive"))
      (node (ref "R9") (pin "2") (pinfunction "2_2") (pintype "passive"))
      (node (ref "U1") (pin "4") (pinfunction "VSS_4") (pintype "power_in"))
      (node (ref "U10") (pin "3") (pinfunction "-_3") (pintype "passive"))
      (node (ref "U2") (pin "1") (pinfunction "GND_1") (pintype "power_in"))
      (node (ref "U3") (pin "1") (pinfunction "GND1_1") (pintype "passive"))
      (node (ref "U3") (pin "18") (pinfunction "AGND_18") (pintype "passive"))
      (node (ref "U3") (pin "29") (pinfunction "VEREF-_29") (pintype "passive"))
      (node (ref "U3") (pin "35") (pinfunction "GND2_35") (pintype "passive"))
      (node (ref "U3") (pin "52") (pinfunction "GND3_52") (pintype "passive"))
      (node (ref "U4") (pin "4") (pinfunction "VSS_4") (pintype "power_in"))
      (node (ref "U4") (pin "8") (pinfunction "VINB-_8") (pintype "passive"))
      (node (ref "U5") (pin "1") (pinfunction "GND_1") (pintype "passive"))
      (node (ref "U6") (pin "1") (pinfunction "GND_1") (pintype "passive"))
      (node (ref "U7") (pin "10") (pinfunction "AD1_10") (pintype "passive"))
      (node (ref "U7") (pin "11") (pinfunction "GND_11") (pintype "passive"))
      (node (ref "U7") (pin "12") (pinfunction "VSS_12") (pintype "passive"))
      (node (ref "U8") (pin "10") (pinfunction "AD1_10") (pintype "passive"))
      (node (ref "U8") (pin "11") (pinfunction "GND_11") (pintype "passive"))
      (node (ref "U8") (pin "12") (pinfunction "VSS_12") (pintype "passive"))
      (node (ref "U8") (pin "9") (pinfunction "AD0_9") (pintype "passive"))
      (node (ref "U9") (pin "11") (pinfunction "Thermal_11") (pintype "passive"))
      (node (ref "U9") (pin "7") (pinfunction "ST~{/M}N_7") (pintype "passive"))
      (node (ref "U9") (pin "8") (pinfunction "GND_8") (pintype "passive"))
      (node (ref "Y1") (pin "2") (pinfunction "GND_2") (pintype "passive"))
    )
    (net (code "80") (name "Net-(C10-Pad1)") (class "Default")
      (node (ref "C10") (pin "1") (pinfunction "1_1") (pintype "passive"))
      (node (ref "R11") (pin "2") (pinfunction "2_2") (pintype "passive"))
    )
    (net (code "81") (name "Net-(C10-Pad2)") (class "Default")
      (node (ref "C10") (pin "2") (pinfunction "2_2") (pintype "passive"))
      (node (ref "MK1") (pin "1") (pinfunction "1_1") (pintype "passive"))
      (node (ref "R10") (pin "2") (pinfunction "2_2") (pintype "passive"))
    )
    (net (code "82") (name "Net-(C23-Pad1)") (class "Default")
      (node (ref "C23") (pin "1") (pinfunction "1_1") (pintype "passive"))
      (node (ref "J1") (pin "5") (pinfunction "5_5") (pintype "passive"))
      (node (ref "LS1") (pin "1") (pinfunction "1_1") (pintype "passive"))
    )
    (net (code "83") (name "Net-(C23-Pad2)") (class "Default")
      (node (ref "C23") (pin "2") (pinfunction "2_2") (pintype "passive"))
      (node (ref "J1") (pin "4") (pinfunction "4_4") (pintype "passive"))
      (node (ref "LS1") (pin "2") (pinfunction "2_2") (pintype "passive"))
    )
    (net (code "84") (name "Net-(C27-Pad1)") (class "Default")
      (node (ref "C27") (pin "1") (pinfunction "1_1") (pintype "passive"))
      (node (ref "R19") (pin "1") (pinfunction "1_1") (pintype "passive"))
    )
    (net (code "85") (name "Net-(D2-A)") (class "Default")
      (node (ref "D2") (pin "1") (pinfunction "A_1") (pintype "passive"))
      (node (ref "R29") (pin "2") (pinfunction "2_2") (pintype "passive"))
    )
    (net (code "86") (name "Net-(D3-A)") (class "Default")
      (node (ref "D3") (pin "1") (pinfunction "A_1") (pintype "passive"))
      (node (ref "R30") (pin "2") (pinfunction "2_2") (pintype "passive"))
    )
    (net (code "87") (name "Net-(D4-A)") (class "Default")
      (node (ref "D4") (pin "1") (pinfunction "A_1") (pintype "passive"))
      (node (ref "R31") (pin "2") (pinfunction "2_2") (pintype "passive"))
    )
    (net (code "88") (name "Net-(R13-Pad1)") (class "Default")
      (node (ref "R13") (pin "1") (pinfunction "1_1") (pintype "passive"))
      (node (ref "R14") (pin "2") (pinfunction "2_2") (pintype "passive"))
      (node (ref "U10") (pin "1") (pinfunction "1_1") (pintype "passive"))
    )
    (net (code "89") (name "Net-(R16-Pad2)") (class "Default")
      (node (ref "R16") (pin "2") (pinfunction "2_2") (pintype "passive"))
      (node (ref "R7") (pin "2") (pinfunction "2_2") (pintype "passive"))
    )
    (net (code "90") (name "Net-(R18-Pad1)") (class "Default")
      (node (ref "R18") (pin "1") (pinfunction "1_1") (pintype "passive"))
      (node (ref "R19") (pin "2") (pinfunction "2_2") (pintype "passive"))
      (node (ref "R32") (pin "1") (pinfunction "1_1") (pintype "passive"))
    )
    (net (code "91") (name "Net-(R21-Pad2)") (class "Default")
      (node (ref "R21") (pin "2") (pinfunction "2_2") (pintype "passive"))
      (node (ref "R25") (pin "1") (pinfunction "1_1") (pintype "passive"))
    )
    (net (code "92") (name "Net-(U1B-VINA+)") (class "Default")
      (node (ref "D1") (pin "1") (pinfunction "1_1") (pintype "passive"))
      (node (ref "R9") (pin "1") (pinfunction "1_1") (pintype "passive"))
      (node (ref "U1") (pin "3") (pinfunction "VINA+_3") (pintype "passive"))
    )
    (net (code "93") (name "Net-(U1B-VOUTA)") (class "Default")
      (node (ref "R6") (pin "1") (pinfunction "1_1") (pintype "passive"))
      (node (ref "R8") (pin "2") (pinfunction "2_2") (pintype "passive"))
      (node (ref "U1") (pin "1") (pinfunction "VOUTA_1") (pintype "passive"))
    )
    (net (code "94") (name "Net-(U1C-VINB+)") (class "Default")
      (node (ref "D1") (pin "2") (pinfunction "2_2") (pintype "passive"))
      (node (ref "R1") (pin "1") (pinfunction "1_1") (pintype "passive"))
      (node (ref "U1") (pin "5") (pinfunction "VINB+_5") (pintype "passive"))
    )
    (net (code "95") (name "Net-(U1C-VOUTB)") (class "Default")
      (node (ref "R22") (pin "2") (pinfunction "2_2") (pintype "passive"))
      (node (ref "R23") (pin "1") (pinfunction "1_1") (pintype "passive"))
      (node (ref "U1") (pin "7") (pinfunction "VOUTB_7") (pintype "passive"))
    )
    (net (code "96") (name "Net-(U4A-~{SHDN}_A)") (class "Default")
      (node (ref "R26") (pin "1") (pinfunction "1_1") (pintype "passive"))
      (node (ref "U4") (pin "5") (pinfunction "~{SHDN}_A_5") (pintype "passive"))
    )
    (net (code "97") (name "Net-(U4A-~{SHDN}_B)") (class "Default")
      (node (ref "R27") (pin "1") (pinfunction "1_1") (pintype "passive"))
      (node (ref "U4") (pin "6") (pinfunction "~{SHDN}_B_6") (pintype "passive"))
    )
    (net (code "98") (name "Net-(U4B-VINA-)") (class "Default")
      (node (ref "C21") (pin "2") (pinfunction "2_2") (pintype "passive"))
      (node (ref "R16") (pin "1") (pinfunction "1_1") (pintype "passive"))
      (node (ref "R21") (pin "1") (pinfunction "1_1") (pintype "passive"))
      (node (ref "U4") (pin "2") (pinfunction "VINA-_2") (pintype "passive"))
    )
    (net (code "99") (name "Net-(U4B-VOUTA)") (class "Default")
      (node (ref "C21") (pin "1") (pinfunction "1_1") (pintype "passive"))
      (node (ref "R20") (pin "1") (pinfunction "1_1") (pintype "passive"))
      (node (ref "R25") (pin "2") (pinfunction "2_2") (pintype "passive"))
      (node (ref "U4") (pin "1") (pinfunction "VOUTA_1") (pintype "passive"))
    )
    (net (code "100") (name "Net-(U4C-VOUTB)") (class "Default")
      (node (ref "R15") (pin "1") (pinfunction "1_1") (pintype "passive"))
      (node (ref "U4") (pin "9") (pinfunction "VOUTB_9") (pintype "passive"))
    )
    (net (code "101") (name "Net-(U6-BUFout)") (class "Default")
      (node (ref "C6") (pin "1") (pinfunction "1_1") (pintype "passive"))
      (node (ref "U6") (pin "4") (pinfunction "BUFout_4") (pintype "passive"))
    )
    (net (code "102") (name "Net-(U6-Cavg)") (class "Default")
      (node (ref "C17") (pin "1") (pinfunction "1_1") (pintype "passive"))
      (node (ref "U6") (pin "6") (pinfunction "Cavg_6") (pintype "passive"))
    )
    (net (code "103") (name "Net-(U6-IN)") (class "Default")
      (node (ref "C11") (pin "1") (pinfunction "1_1") (pintype "passive"))
      (node (ref "R11") (pin "1") (pinfunction "1_1") (pintype "passive"))
      (node (ref "U6") (pin "5") (pinfunction "IN_5") (pintype "passive"))
    )
    (net (code "104") (name "Net-(U6-OUT)") (class "Default")
      (node (ref "R7") (pin "1") (pinfunction "1_1") (pintype "passive"))
      (node (ref "U6") (pin "9") (pinfunction "OUT_9") (pintype "passive"))
    )
    (net (code "105") (name "Net-(U6-VCAin)") (class "Default")
      (node (ref "C6") (pin "2") (pinfunction "2_2") (pintype "passive"))
      (node (ref "U6") (pin "2") (pinfunction "VCAin_2") (pintype "passive"))
    )
    (net (code "106") (name "Net-(U7-A2)") (class "Default")
      (node (ref "R34") (pin "1") (pinfunction "1_1") (pintype "passive"))
      (node (ref "U7") (pin "16") (pinfunction "A2_16") (pintype "passive"))
    )
    (net (code "107") (name "Net-(U7-W2)") (class "Default")
      (node (ref "R33") (pin "1") (pinfunction "1_1") (pintype "passive"))
      (node (ref "U7") (pin "15") (pinfunction "W2_15") (pintype "passive"))
    )
    (net (code "108") (name "Net-(U9-Bypass)") (class "Default")
      (node (ref "C18") (pin "1") (pinfunction "1_1") (pintype "passive"))
      (node (ref "U9") (pin "4") (pinfunction "Bypass_4") (pintype "passive"))
    )
    (net (code "109") (name "Net-(U9-FILT_CAP)") (class "Default")
      (node (ref "C19") (pin "2") (pinfunction "2_2") (pintype "passive"))
      (node (ref "U9") (pin "1") (pinfunction "FILT_CAP_1") (pintype "passive"))
    )
    (net (code "110") (name "Net-(U9-LO)") (class "Default")
      (node (ref "J1") (pin "3") (pinfunction "3_3") (pintype "passive"))
      (node (ref "U9") (pin "10") (pinfunction "LO_10") (pintype "passive"))
    )
    (net (code "111") (name "Net-(U9-Lin)") (class "Default")
      (node (ref "R32") (pin "2") (pinfunction "2_2") (pintype "passive"))
      (node (ref "R35") (pin "2") (pinfunction "2_2") (pintype "passive"))
      (node (ref "U9") (pin "9") (pinfunction "Lin_9") (pintype "passive"))
    )
    (net (code "112") (name "Net-(U9-RO)") (class "Default")
      (node (ref "J1") (pin "2") (pinfunction "2_2") (pintype "passive"))
      (node (ref "U9") (pin "6") (pinfunction "RO_6") (pintype "passive"))
    )
    (net (code "113") (name "Net-(U9-Rin)") (class "Default")
      (node (ref "R18") (pin "2") (pinfunction "2_2") (pintype "passive"))
      (node (ref "R36") (pin "2") (pinfunction "2_2") (pintype "passive"))
      (node (ref "U9") (pin "5") (pinfunction "Rin_5") (pintype "passive"))
    )
    (net (code "114") (name "unconnected-(P1-Pad2)") (class "Default")
      (node (ref "P1") (pin "2") (pinfunction "2_2") (pintype "passive"))
    )
    (net (code "115") (name "unconnected-(P2-Pad6)") (class "Default")
      (node (ref "P2") (pin "6") (pinfunction "6_6") (pintype "passive+no_connect"))
    )
    (net (code "116") (name "unconnected-(U7-A1-Pad2)") (class "Default")
      (node (ref "U7") (pin "2") (pinfunction "A1_2") (pintype "passive+no_connect"))
    )
    (net (code "117") (name "unconnected-(U7-B2-Pad14)") (class "Default")
      (node (ref "U7") (pin "14") (pinfunction "B2_14") (pintype "passive+no_connect"))
    )
    (net (code "118") (name "unconnected-(U7-O1-Pad1)") (class "Default")
      (node (ref "U7") (pin "1") (pinfunction "O1_1") (pintype "passive+no_connect"))
    )
    (net (code "119") (name "unconnected-(U7-O2-Pad13)") (class "Default")
      (node (ref "U7") (pin "13") (pinfunction "O2_13") (pintype "passive+no_connect"))
    )
    (net (code "120") (name "unconnected-(U8-A1-Pad2)") (class "Default")
      (node (ref "U8") (pin "2") (pinfunction "A1_2") (pintype "passive+no_connect"))
    )
    (net (code "121") (name "unconnected-(U8-A2-Pad16)") (class "Default")
      (node (ref "U8") (pin "16") (pinfunction "A2_16") (pintype "passive+no_connect"))
    )
    (net (code "122") (name "unconnected-(U8-B2-Pad14)") (class "Default")
      (node (ref "U8") (pin "14") (pinfunction "B2_14") (pintype "passive+no_connect"))
    )
    (net (code "123") (name "unconnected-(U8-O1-Pad1)") (class "Default")
      (node (ref "U8") (pin "1") (pinfunction "O1_1") (pintype "passive+no_connect"))
    )
    (net (code "124") (name "unconnected-(U8-O2-Pad13)") (class "Default")
      (node (ref "U8") (pin "13") (pinfunction "O2_13") (pintype "passive+no_connect"))
    )
    (net (code "125") (name "unconnected-(U8-W2-Pad15)") (class "Default")
      (node (ref "U8") (pin "15") (pinfunction "W2_15") (pintype "passive+no_connect"))
    )
  )
)
